# MinipHV3_1.net
KiCad netlist of a schematic drawn in EAGLE
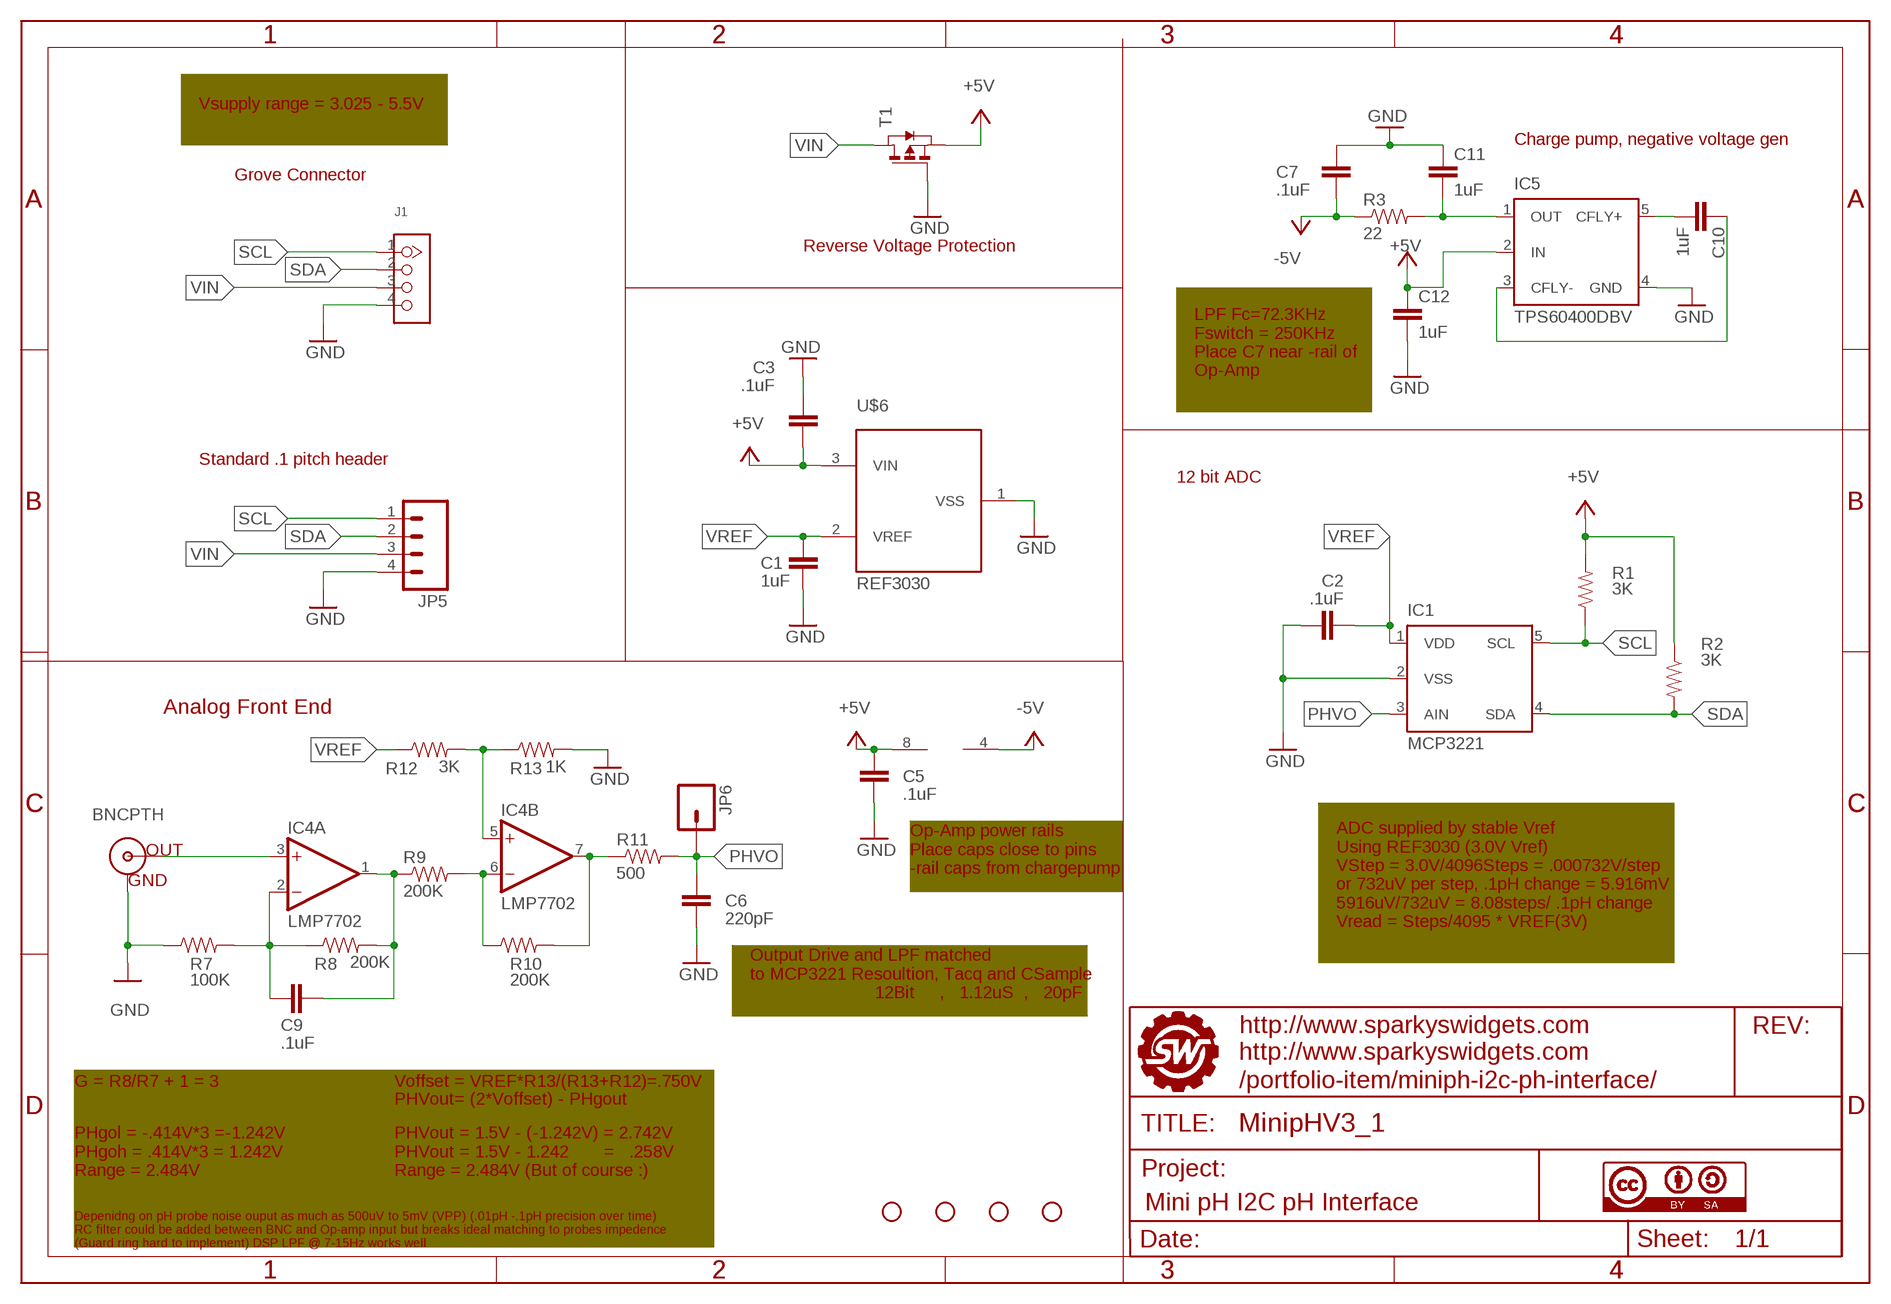
[diagram p0: schematic, sheet 1]

(export (version "E")
  (design (tool "Eeschema 10.0.6"))
  (components
    (comp (ref "C1")
      (value "1uF")
      (footprint "eagle-import:0805")
      (libsource (lib "eagle-import") (part "CAP0805"))
    )
    (comp (ref "C2")
      (value ".1uF")
      (footprint "eagle-import:0805")
      (libsource (lib "eagle-import") (part "CAP0805"))
    )
    (comp (ref "C3")
      (value ".1uF")
      (footprint "eagle-import:0805")
      (libsource (lib "eagle-import") (part "CAP0805"))
    )
    (comp (ref "C5")
      (value ".1uF")
      (footprint "eagle-import:0805")
      (libsource (lib "eagle-import") (part "CAP0805"))
    )
    (comp (ref "C6")
      (value "220pF")
      (footprint "eagle-import:0805")
      (libsource (lib "eagle-import") (part "CAP0805"))
    )
    (comp (ref "C7")
      (value ".1uF")
      (footprint "eagle-import:0805")
      (libsource (lib "eagle-import") (part "CAP0805"))
    )
    (comp (ref "C9")
      (value ".1uF")
      (footprint "eagle-import:0805")
      (libsource (lib "eagle-import") (part "CAP0805"))
    )
    (comp (ref "C10")
      (value "1uF")
      (footprint "eagle-import:0805")
      (libsource (lib "eagle-import") (part "CAP0805"))
    )
    (comp (ref "C11")
      (value "1uF")
      (footprint "eagle-import:0805")
      (libsource (lib "eagle-import") (part "CAP0805"))
    )
    (comp (ref "C12")
      (value "1uF")
      (footprint "eagle-import:0805")
      (libsource (lib "eagle-import") (part "CAP0805"))
    )
    (comp (ref "IC1")
      (value "MCP3221")
      (footprint "eagle-import:SOT23-DBV")
      (libsource (lib "eagle-import") (part "MCP3221"))
    )
    (comp (ref "IC4")
      (value "LMP7702")
      (footprint "eagle-import:SO08")
      (libsource (lib "eagle-import") (part "LM358D"))
    )
    (comp (ref "IC5")
      (value "TPS60400DBV")
      (footprint "eagle-import:SOT23-DBV")
      (libsource (lib "eagle-import") (part "TPS60400DBV"))
    )
    (comp (ref "J1")
      (value "TWIG-4P-2.0-2.0")
      (footprint "eagle-import:4P-2.0")
      (libsource (lib "eagle-import") (part "TWIG-4P-2.0-2.0"))
    )
    (comp (ref "JP1")
      (value "STAND-OFF")
      (footprint "eagle-import:STAND-OFF")
      (libsource (lib "eagle-import") (part "STAND-OFF"))
    )
    (comp (ref "JP2")
      (value "STAND-OFF")
      (footprint "eagle-import:STAND-OFF")
      (libsource (lib "eagle-import") (part "STAND-OFF"))
    )
    (comp (ref "JP3")
      (value "STAND-OFF")
      (footprint "eagle-import:STAND-OFF")
      (libsource (lib "eagle-import") (part "STAND-OFF"))
    )
    (comp (ref "JP4")
      (value "STAND-OFF")
      (footprint "eagle-import:STAND-OFF")
      (libsource (lib "eagle-import") (part "STAND-OFF"))
    )
    (comp (ref "JP5")
      (value "M04PTH")
      (footprint "eagle-import:1X04")
      (libsource (lib "eagle-import") (part "M04PTH"))
    )
    (comp (ref "JP6")
      (value "M01PTH")
      (footprint "eagle-import:1X01")
      (libsource (lib "eagle-import") (part "M01PTH"))
    )
    (comp (ref "R1")
      (value "3K")
      (footprint "eagle-import:0805")
      (libsource (lib "eagle-import") (part "RESISTOR0805-RES"))
    )
    (comp (ref "R2")
      (value "3K")
      (footprint "eagle-import:0805")
      (libsource (lib "eagle-import") (part "RESISTOR0805-RES"))
    )
    (comp (ref "R3")
      (value "22")
      (footprint "eagle-import:0805")
      (libsource (lib "eagle-import") (part "RESISTOR0805-RES"))
    )
    (comp (ref "R7")
      (value "100K")
      (footprint "eagle-import:0805")
      (libsource (lib "eagle-import") (part "RESISTOR0805-RES"))
    )
    (comp (ref "R8")
      (value "200K")
      (footprint "eagle-import:0805")
      (libsource (lib "eagle-import") (part "RESISTOR0805-RES"))
    )
    (comp (ref "R9")
      (value "200K")
      (footprint "eagle-import:0805")
      (libsource (lib "eagle-import") (part "RESISTOR0805-RES"))
    )
    (comp (ref "R10")
      (value "200K")
      (footprint "eagle-import:0805")
      (libsource (lib "eagle-import") (part "RESISTOR0805-RES"))
    )
    (comp (ref "R11")
      (value "500")
      (footprint "eagle-import:0805")
      (libsource (lib "eagle-import") (part "RESISTOR0805-RES"))
    )
    (comp (ref "R12")
      (value "3K")
      (footprint "eagle-import:0805")
      (libsource (lib "eagle-import") (part "RESISTOR0805-RES"))
    )
    (comp (ref "R13")
      (value "1K")
      (footprint "eagle-import:0805")
      (libsource (lib "eagle-import") (part "RESISTOR0805-RES"))
    )
    (comp (ref "T1")
      (value "PMOSSOT23")
      (footprint "eagle-import:SOT-23")
      (libsource (lib "eagle-import") (part "PMOSSOT23"))
    )
    (comp (ref "U$2")
      (value "BNCPTH")
      (footprint "eagle-import:BNC")
      (libsource (lib "eagle-import") (part "BNCPTH"))
    )
    (comp (ref "U$4")
      (value "FRAME_MINIPH")
      (footprint "eagle-import:SWPCBLOGOWITHINFO")
      (fields
        (field (name "PROJECT") "Mini pH I2C pH Interface")
        (field (name "URL1") "/portfolio-item/miniph-i2c-ph-interface/")
      )
      (libsource (lib "eagle-import") (part "FRAME_MINIPH"))
    )
    (comp (ref "U$5")
      (value "CC-BY-SA")
      (footprint "eagle-import:CC-BY-SA")
      (libsource (lib "eagle-import") (part "CC-BY-SA"))
    )
    (comp (ref "U$6")
      (value "REF3030")
      (footprint "eagle-import:SOT-23")
      (libsource (lib "eagle-import") (part "MCP1541"))
    )
  )
  (nets
    (net (code "1") (name "+5V") (class "Default")
      (node (ref "C12") (pin "1") (pinfunction "1_1") (pintype "passive"))
      (node (ref "C3") (pin "1") (pinfunction "1_1") (pintype "passive"))
      (node (ref "C5") (pin "1") (pinfunction "1_1") (pintype "passive"))
      (node (ref "IC4") (pin "8") (pinfunction "V+_8") (pintype "power_in"))
      (node (ref "IC5") (pin "2") (pinfunction "IN_2") (pintype "input"))
      (node (ref "R1") (pin "2") (pinfunction "2_2") (pintype "passive"))
      (node (ref "R2") (pin "1") (pinfunction "1_1") (pintype "passive"))
      (node (ref "T1") (pin "2") (pinfunction "S_2") (pintype "passive"))
      (node (ref "U$6") (pin "3") (pinfunction "VIN_3") (pintype "power_in"))
    )
    (net (code "2") (name "-5V") (class "Default")
      (node (ref "C7") (pin "2") (pinfunction "2_2") (pintype "passive"))
      (node (ref "IC4") (pin "4") (pinfunction "V-_4") (pintype "power_in"))
      (node (ref "R3") (pin "1") (pinfunction "1_1") (pintype "passive"))
    )
    (net (code "3") (name "GND") (class "Default")
      (node (ref "C1") (pin "2") (pinfunction "2_2") (pintype "passive"))
      (node (ref "C11") (pin "1") (pinfunction "1_1") (pintype "passive"))
      (node (ref "C12") (pin "2") (pinfunction "2_2") (pintype "passive"))
      (node (ref "C2") (pin "1") (pinfunction "1_1") (pintype "passive"))
      (node (ref "C3") (pin "2") (pinfunction "2_2") (pintype "passive"))
      (node (ref "C5") (pin "2") (pinfunction "2_2") (pintype "passive"))
      (node (ref "C6") (pin "2") (pinfunction "2_2") (pintype "passive"))
      (node (ref "C7") (pin "1") (pinfunction "1_1") (pintype "passive"))
      (node (ref "IC1") (pin "2") (pinfunction "VSS_2") (pintype "power_in"))
      (node (ref "IC5") (pin "4") (pinfunction "GND_4") (pintype "passive"))
      (node (ref "J1") (pin "4") (pinfunction "4_4") (pintype "bidirectional"))
      (node (ref "JP5") (pin "4") (pinfunction "4_4") (pintype "passive"))
      (node (ref "R13") (pin "2") (pinfunction "2_2") (pintype "passive"))
      (node (ref "R7") (pin "1") (pinfunction "1_1") (pintype "passive"))
      (node (ref "T1") (pin "3") (pinfunction "G_3") (pintype "passive"))
      (node (ref "U$2") (pin "GND") (pinfunction "GND_GND") (pintype "bidirectional"))
      (node (ref "U$6") (pin "1") (pinfunction "VSS_1") (pintype "power_in"))
    )
    (net (code "4") (name "Net-(IC4A-+IN)") (class "Default")
      (node (ref "IC4") (pin "3") (pinfunction "+IN_3") (pintype "input"))
      (node (ref "U$2") (pin "S") (pinfunction "OUT_S") (pintype "bidirectional"))
    )
    (net (code "5") (name "Net-(IC4A--IN)") (class "Default")
      (node (ref "C9") (pin "2") (pinfunction "2_2") (pintype "passive"))
      (node (ref "IC4") (pin "2") (pinfunction "-IN_2") (pintype "input"))
      (node (ref "R7") (pin "2") (pinfunction "2_2") (pintype "passive"))
      (node (ref "R8") (pin "1") (pinfunction "1_1") (pintype "passive"))
    )
    (net (code "6") (name "Net-(IC4A-OUT)") (class "Default")
      (node (ref "C9") (pin "1") (pinfunction "1_1") (pintype "passive"))
      (node (ref "IC4") (pin "1") (pinfunction "OUT_1") (pintype "output"))
      (node (ref "R8") (pin "2") (pinfunction "2_2") (pintype "passive"))
      (node (ref "R9") (pin "1") (pinfunction "1_1") (pintype "passive"))
    )
    (net (code "7") (name "Net-(IC4B-+IN)") (class "Default")
      (node (ref "IC4") (pin "5") (pinfunction "+IN_5") (pintype "input"))
      (node (ref "R12") (pin "2") (pinfunction "2_2") (pintype "passive"))
      (node (ref "R13") (pin "1") (pinfunction "1_1") (pintype "passive"))
    )
    (net (code "8") (name "Net-(IC4B--IN)") (class "Default")
      (node (ref "IC4") (pin "6") (pinfunction "-IN_6") (pintype "input"))
      (node (ref "R10") (pin "1") (pinfunction "1_1") (pintype "passive"))
      (node (ref "R9") (pin "2") (pinfunction "2_2") (pintype "passive"))
    )
    (net (code "9") (name "Net-(IC4B-OUT)") (class "Default")
      (node (ref "IC4") (pin "7") (pinfunction "OUT_7") (pintype "output"))
      (node (ref "R10") (pin "2") (pinfunction "2_2") (pintype "passive"))
      (node (ref "R11") (pin "1") (pinfunction "1_1") (pintype "passive"))
    )
    (net (code "10") (name "Net-(IC5-CFLY+)") (class "Default")
      (node (ref "C10") (pin "2") (pinfunction "2_2") (pintype "passive"))
      (node (ref "IC5") (pin "5") (pinfunction "CFLY+_5") (pintype "passive"))
    )
    (net (code "11") (name "Net-(IC5-CFLY-)") (class "Default")
      (node (ref "C10") (pin "1") (pinfunction "1_1") (pintype "passive"))
      (node (ref "IC5") (pin "3") (pinfunction "CFLY-_3") (pintype "power_in"))
    )
    (net (code "12") (name "Net-(IC5-OUT)") (class "Default")
      (node (ref "C11") (pin "2") (pinfunction "2_2") (pintype "passive"))
      (node (ref "IC5") (pin "1") (pinfunction "OUT_1") (pintype "input"))
      (node (ref "R3") (pin "2") (pinfunction "2_2") (pintype "passive"))
    )
    (net (code "13") (name "PHVO") (class "Default")
      (node (ref "C6") (pin "1") (pinfunction "1_1") (pintype "passive"))
      (node (ref "IC1") (pin "3") (pinfunction "AIN_3") (pintype "input"))
      (node (ref "JP6") (pin "1") (pinfunction "1_1") (pintype "passive"))
      (node (ref "R11") (pin "2") (pinfunction "2_2") (pintype "passive"))
    )
    (net (code "14") (name "SCL") (class "Default")
      (node (ref "IC1") (pin "5") (pinfunction "SCL_5") (pintype "bidirectional"))
      (node (ref "J1") (pin "1") (pinfunction "1_1") (pintype "bidirectional"))
      (node (ref "JP5") (pin "1") (pinfunction "1_1") (pintype "passive"))
      (node (ref "R1") (pin "1") (pinfunction "1_1") (pintype "passive"))
    )
    (net (code "15") (name "SDA") (class "Default")
      (node (ref "IC1") (pin "4") (pinfunction "SDA_4") (pintype "bidirectional"))
      (node (ref "J1") (pin "2") (pinfunction "2_2") (pintype "bidirectional"))
      (node (ref "JP5") (pin "2") (pinfunction "2_2") (pintype "passive"))
      (node (ref "R2") (pin "2") (pinfunction "2_2") (pintype "passive"))
    )
    (net (code "16") (name "VIN") (class "Default")
      (node (ref "J1") (pin "3") (pinfunction "3_3") (pintype "bidirectional"))
      (node (ref "JP5") (pin "3") (pinfunction "3_3") (pintype "passive"))
      (node (ref "T1") (pin "1") (pinfunction "D_1") (pintype "passive"))
    )
    (net (code "17") (name "VREF") (class "Default")
      (node (ref "C1") (pin "1") (pinfunction "1_1") (pintype "passive"))
      (node (ref "C2") (pin "2") (pinfunction "2_2") (pintype "passive"))
      (node (ref "IC1") (pin "1") (pinfunction "VDD_1") (pintype "power_in"))
      (node (ref "R12") (pin "1") (pinfunction "1_1") (pintype "passive"))
      (node (ref "U$6") (pin "2") (pinfunction "VREF_2") (pintype "output"))
    )
  )
)
